# prob.net
KiCad netlist of a schematic drawn in EasyEDA
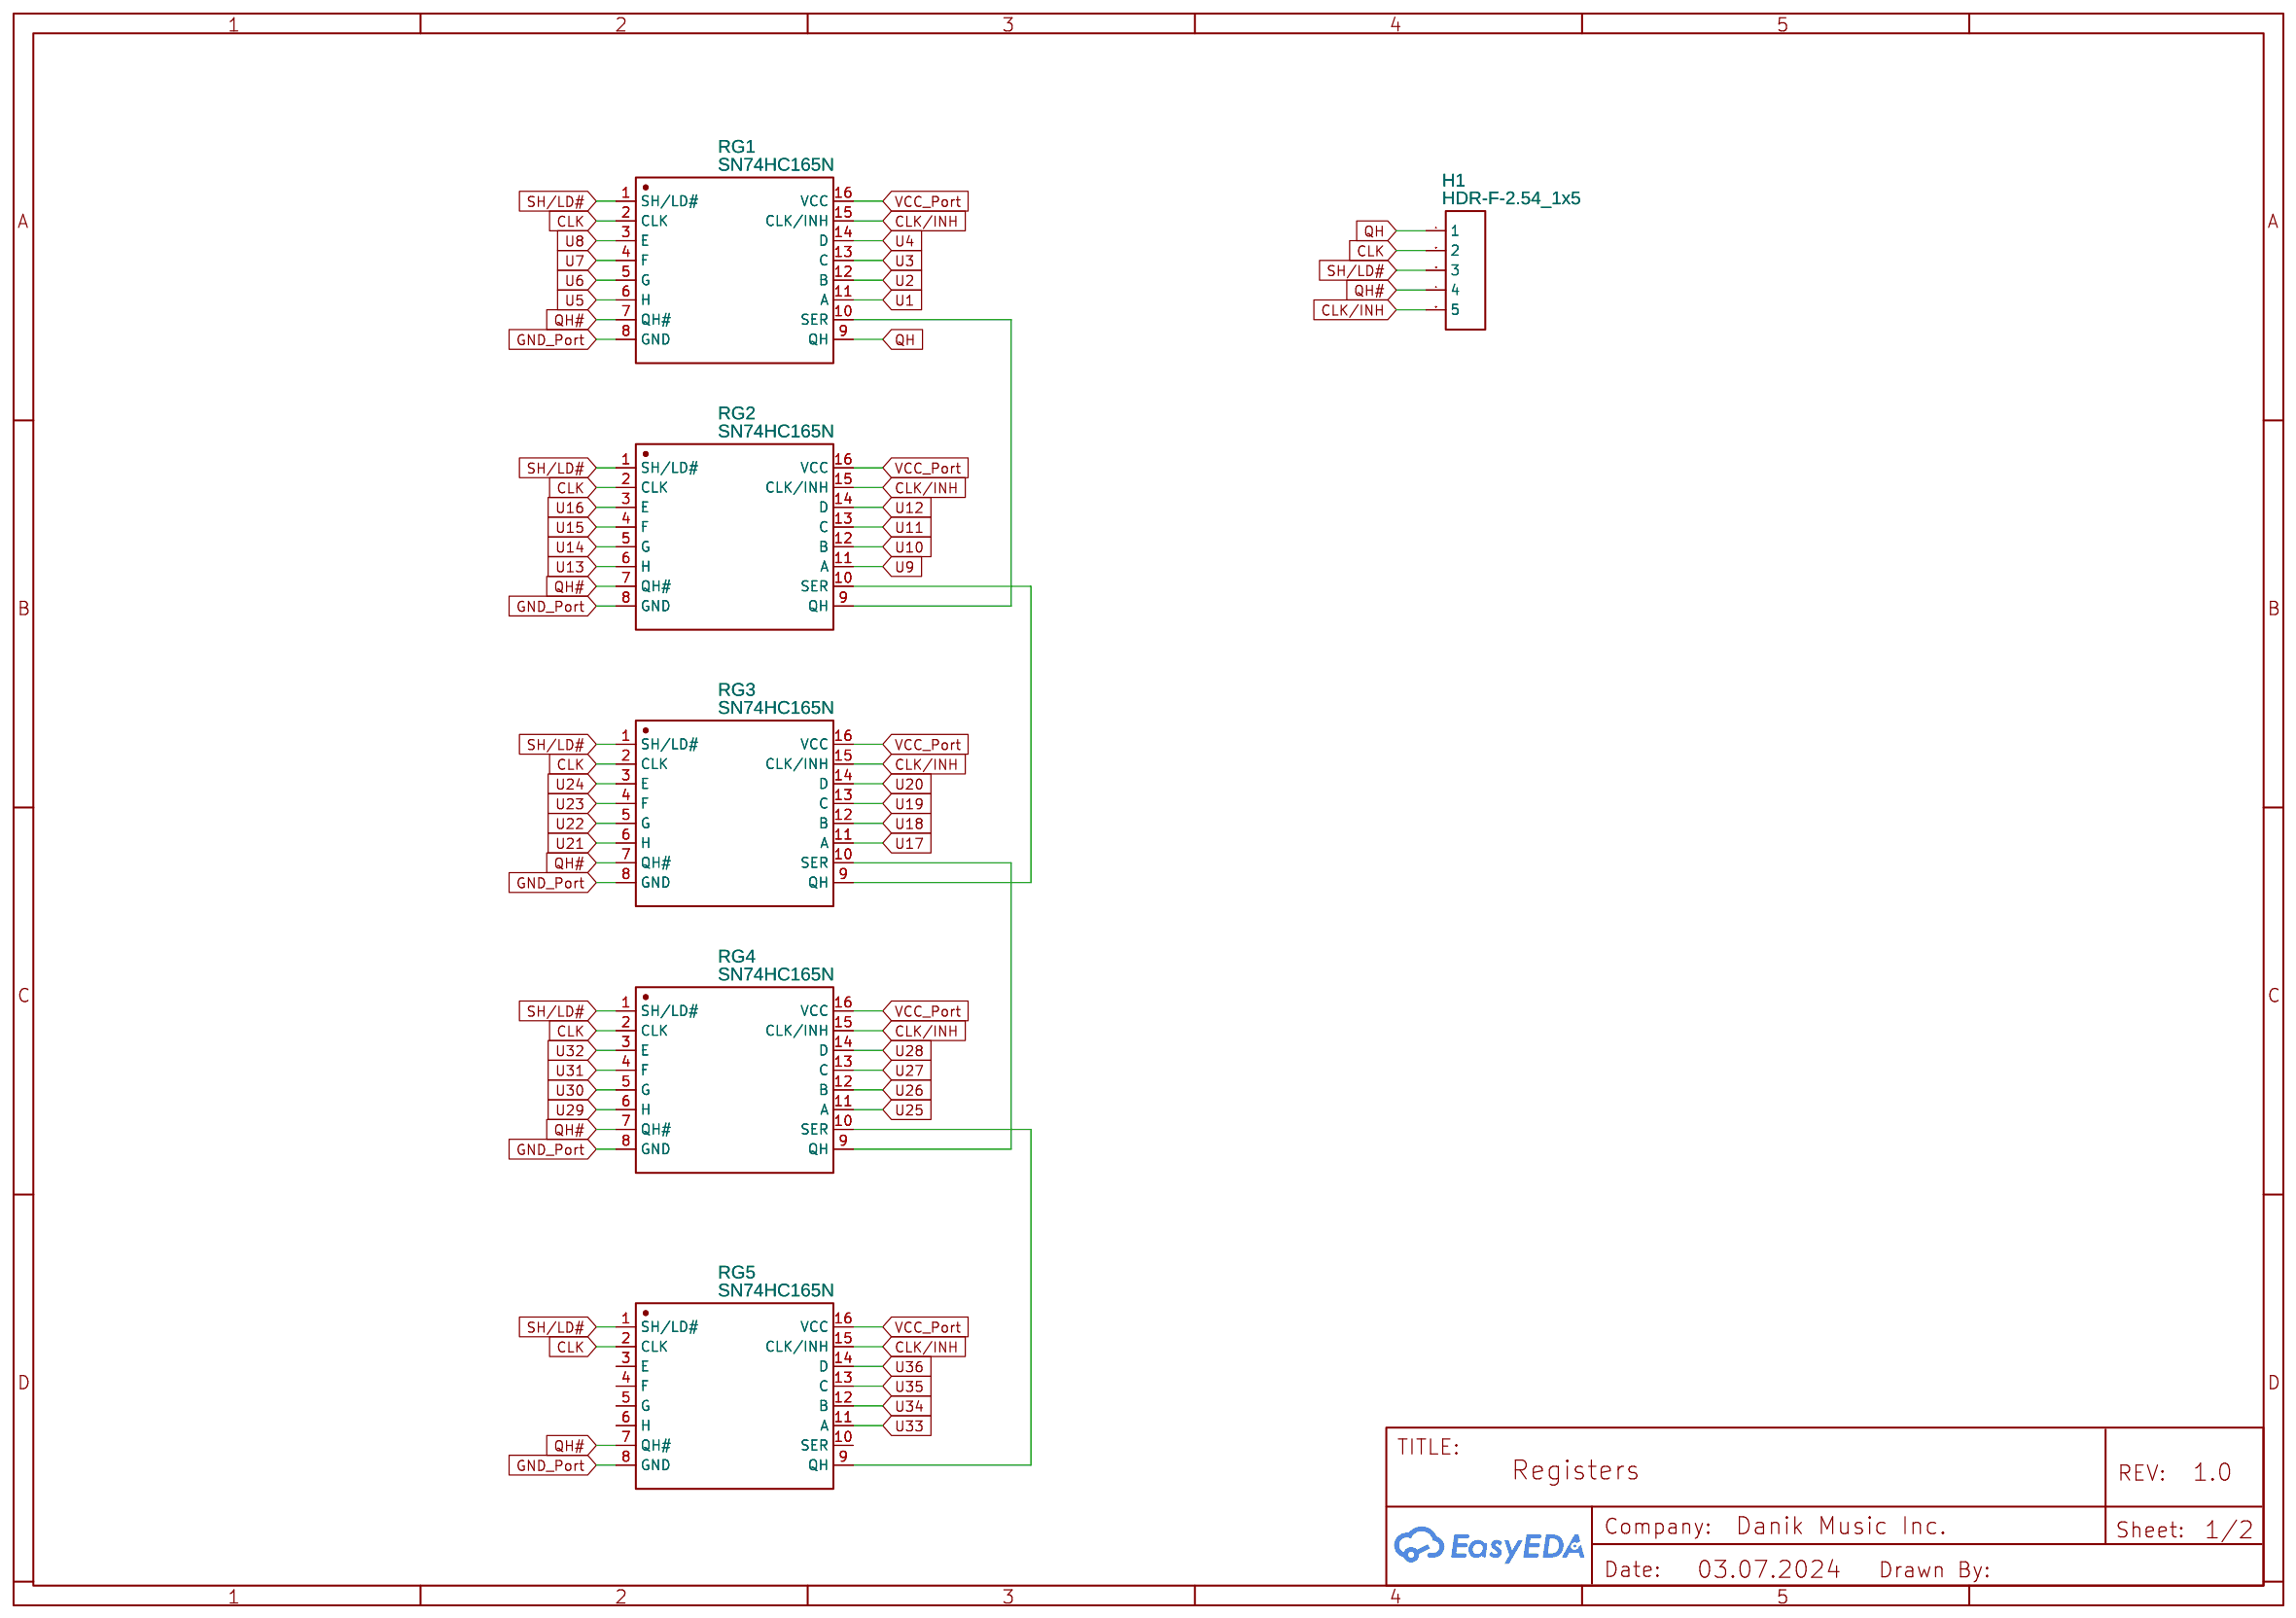
[diagram p0: Регистры]
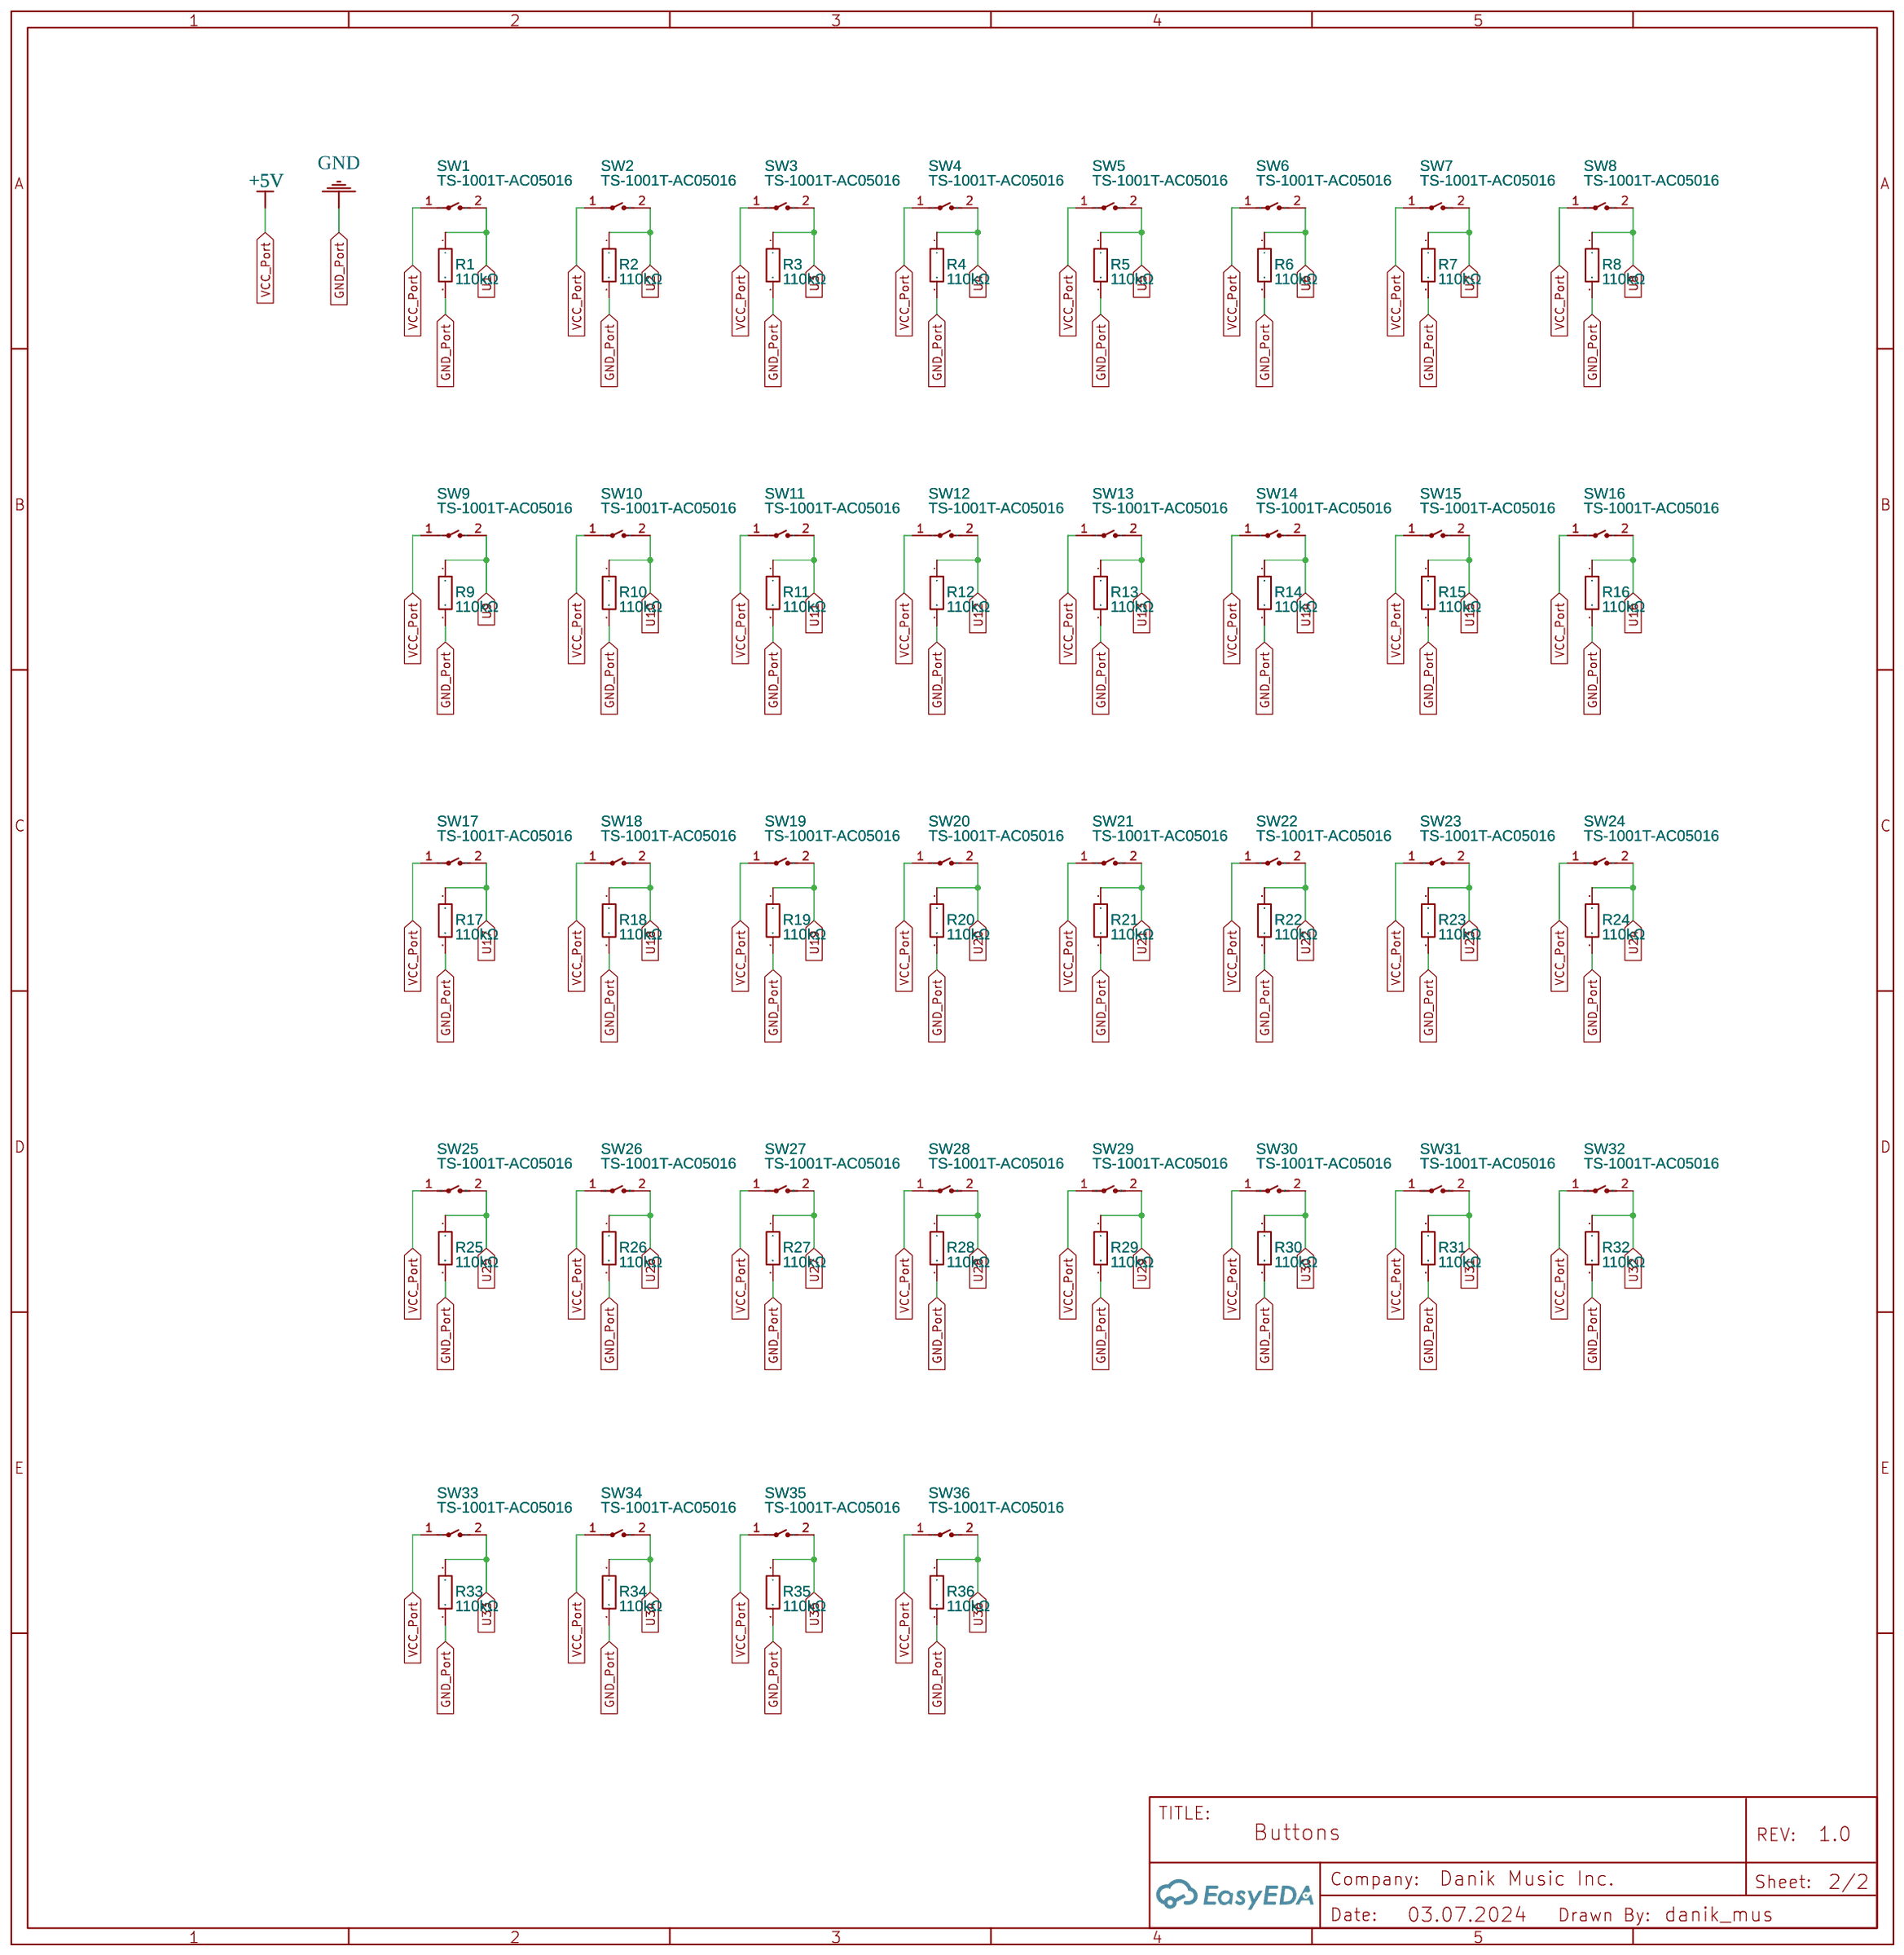
[diagram p1: Кнопки]

(export (version "E")
  (design (tool "Eeschema 10.0.6"))
  (components
    (comp (ref "H1") (value "HDR-F-2.54_1x5") (libsource (lib "") (part "HDR-F-2.54_1x5")))
    (comp (ref "RG1")
      (value "SN74HC165N")
      (fields (field (name "Manufacturer") "TI(德州仪器)"))
      (libsource (lib "") (part "SN74HC165N"))
    )
    (comp (ref "RG2")
      (value "SN74HC165N")
      (fields (field (name "Manufacturer") "TI(德州仪器)"))
      (libsource (lib "") (part "SN74HC165N"))
    )
    (comp (ref "RG3")
      (value "SN74HC165N")
      (fields (field (name "Manufacturer") "TI(德州仪器)"))
      (libsource (lib "") (part "SN74HC165N"))
    )
    (comp (ref "RG4")
      (value "SN74HC165N")
      (fields (field (name "Manufacturer") "TI(德州仪器)"))
      (libsource (lib "") (part "SN74HC165N"))
    )
    (comp (ref "RG5")
      (value "SN74HC165N")
      (fields (field (name "Manufacturer") "TI(德州仪器)"))
      (libsource (lib "") (part "SN74HC165N"))
    )
    (comp (ref "R1")
      (value "110kΩ")
      (fields
        (field (name "Manufacturer Part") "CF1/4W-110KΩ±5% T52")
        (field (name "Manufacturer") "CCO(千志电子)")
      )
      (libsource (lib "") (part "CF1/4W-110KΩ±5% T52"))
    )
    (comp (ref "R2")
      (value "110kΩ")
      (fields
        (field (name "Manufacturer Part") "CF1/4W-110KΩ±5% T52")
        (field (name "Manufacturer") "CCO(千志电子)")
      )
      (libsource (lib "") (part "CF1/4W-110KΩ±5% T52"))
    )
    (comp (ref "R3")
      (value "110kΩ")
      (fields
        (field (name "Manufacturer Part") "CF1/4W-110KΩ±5% T52")
        (field (name "Manufacturer") "CCO(千志电子)")
      )
      (libsource (lib "") (part "CF1/4W-110KΩ±5% T52"))
    )
    (comp (ref "R4")
      (value "110kΩ")
      (fields
        (field (name "Manufacturer Part") "CF1/4W-110KΩ±5% T52")
        (field (name "Manufacturer") "CCO(千志电子)")
      )
      (libsource (lib "") (part "CF1/4W-110KΩ±5% T52"))
    )
    (comp (ref "R5")
      (value "110kΩ")
      (fields
        (field (name "Manufacturer Part") "CF1/4W-110KΩ±5% T52")
        (field (name "Manufacturer") "CCO(千志电子)")
      )
      (libsource (lib "") (part "CF1/4W-110KΩ±5% T52"))
    )
    (comp (ref "R6")
      (value "110kΩ")
      (fields
        (field (name "Manufacturer Part") "CF1/4W-110KΩ±5% T52")
        (field (name "Manufacturer") "CCO(千志电子)")
      )
      (libsource (lib "") (part "CF1/4W-110KΩ±5% T52"))
    )
    (comp (ref "R7")
      (value "110kΩ")
      (fields
        (field (name "Manufacturer Part") "CF1/4W-110KΩ±5% T52")
        (field (name "Manufacturer") "CCO(千志电子)")
      )
      (libsource (lib "") (part "CF1/4W-110KΩ±5% T52"))
    )
    (comp (ref "R8")
      (value "110kΩ")
      (fields
        (field (name "Manufacturer Part") "CF1/4W-110KΩ±5% T52")
        (field (name "Manufacturer") "CCO(千志电子)")
      )
      (libsource (lib "") (part "CF1/4W-110KΩ±5% T52"))
    )
    (comp (ref "R9")
      (value "110kΩ")
      (fields
        (field (name "Manufacturer Part") "CF1/4W-110KΩ±5% T52")
        (field (name "Manufacturer") "CCO(千志电子)")
      )
      (libsource (lib "") (part "CF1/4W-110KΩ±5% T52"))
    )
    (comp (ref "R10")
      (value "110kΩ")
      (fields
        (field (name "Manufacturer Part") "CF1/4W-110KΩ±5% T52")
        (field (name "Manufacturer") "CCO(千志电子)")
      )
      (libsource (lib "") (part "CF1/4W-110KΩ±5% T52"))
    )
    (comp (ref "R11")
      (value "110kΩ")
      (fields
        (field (name "Manufacturer Part") "CF1/4W-110KΩ±5% T52")
        (field (name "Manufacturer") "CCO(千志电子)")
      )
      (libsource (lib "") (part "CF1/4W-110KΩ±5% T52"))
    )
    (comp (ref "R12")
      (value "110kΩ")
      (fields
        (field (name "Manufacturer Part") "CF1/4W-110KΩ±5% T52")
        (field (name "Manufacturer") "CCO(千志电子)")
      )
      (libsource (lib "") (part "CF1/4W-110KΩ±5% T52"))
    )
    (comp (ref "R13")
      (value "110kΩ")
      (fields
        (field (name "Manufacturer Part") "CF1/4W-110KΩ±5% T52")
        (field (name "Manufacturer") "CCO(千志电子)")
      )
      (libsource (lib "") (part "CF1/4W-110KΩ±5% T52"))
    )
    (comp (ref "R14")
      (value "110kΩ")
      (fields
        (field (name "Manufacturer Part") "CF1/4W-110KΩ±5% T52")
        (field (name "Manufacturer") "CCO(千志电子)")
      )
      (libsource (lib "") (part "CF1/4W-110KΩ±5% T52"))
    )
    (comp (ref "R15")
      (value "110kΩ")
      (fields
        (field (name "Manufacturer Part") "CF1/4W-110KΩ±5% T52")
        (field (name "Manufacturer") "CCO(千志电子)")
      )
      (libsource (lib "") (part "CF1/4W-110KΩ±5% T52"))
    )
    (comp (ref "R16")
      (value "110kΩ")
      (fields
        (field (name "Manufacturer Part") "CF1/4W-110KΩ±5% T52")
        (field (name "Manufacturer") "CCO(千志电子)")
      )
      (libsource (lib "") (part "CF1/4W-110KΩ±5% T52"))
    )
    (comp (ref "R17")
      (value "110kΩ")
      (fields
        (field (name "Manufacturer Part") "CF1/4W-110KΩ±5% T52")
        (field (name "Manufacturer") "CCO(千志电子)")
      )
      (libsource (lib "") (part "CF1/4W-110KΩ±5% T52"))
    )
    (comp (ref "R18")
      (value "110kΩ")
      (fields
        (field (name "Manufacturer Part") "CF1/4W-110KΩ±5% T52")
        (field (name "Manufacturer") "CCO(千志电子)")
      )
      (libsource (lib "") (part "CF1/4W-110KΩ±5% T52"))
    )
    (comp (ref "R19")
      (value "110kΩ")
      (fields
        (field (name "Manufacturer Part") "CF1/4W-110KΩ±5% T52")
        (field (name "Manufacturer") "CCO(千志电子)")
      )
      (libsource (lib "") (part "CF1/4W-110KΩ±5% T52"))
    )
    (comp (ref "R20")
      (value "110kΩ")
      (fields
        (field (name "Manufacturer Part") "CF1/4W-110KΩ±5% T52")
        (field (name "Manufacturer") "CCO(千志电子)")
      )
      (libsource (lib "") (part "CF1/4W-110KΩ±5% T52"))
    )
    (comp (ref "R21")
      (value "110kΩ")
      (fields
        (field (name "Manufacturer Part") "CF1/4W-110KΩ±5% T52")
        (field (name "Manufacturer") "CCO(千志电子)")
      )
      (libsource (lib "") (part "CF1/4W-110KΩ±5% T52"))
    )
    (comp (ref "R22")
      (value "110kΩ")
      (fields
        (field (name "Manufacturer Part") "CF1/4W-110KΩ±5% T52")
        (field (name "Manufacturer") "CCO(千志电子)")
      )
      (libsource (lib "") (part "CF1/4W-110KΩ±5% T52"))
    )
    (comp (ref "R23")
      (value "110kΩ")
      (fields
        (field (name "Manufacturer Part") "CF1/4W-110KΩ±5% T52")
        (field (name "Manufacturer") "CCO(千志电子)")
      )
      (libsource (lib "") (part "CF1/4W-110KΩ±5% T52"))
    )
    (comp (ref "R24")
      (value "110kΩ")
      (fields
        (field (name "Manufacturer Part") "CF1/4W-110KΩ±5% T52")
        (field (name "Manufacturer") "CCO(千志电子)")
      )
      (libsource (lib "") (part "CF1/4W-110KΩ±5% T52"))
    )
    (comp (ref "R25")
      (value "110kΩ")
      (fields
        (field (name "Manufacturer Part") "CF1/4W-110KΩ±5% T52")
        (field (name "Manufacturer") "CCO(千志电子)")
      )
      (libsource (lib "") (part "CF1/4W-110KΩ±5% T52"))
    )
    (comp (ref "R26")
      (value "110kΩ")
      (fields
        (field (name "Manufacturer Part") "CF1/4W-110KΩ±5% T52")
        (field (name "Manufacturer") "CCO(千志电子)")
      )
      (libsource (lib "") (part "CF1/4W-110KΩ±5% T52"))
    )
    (comp (ref "R27")
      (value "110kΩ")
      (fields
        (field (name "Manufacturer Part") "CF1/4W-110KΩ±5% T52")
        (field (name "Manufacturer") "CCO(千志电子)")
      )
      (libsource (lib "") (part "CF1/4W-110KΩ±5% T52"))
    )
    (comp (ref "R28")
      (value "110kΩ")
      (fields
        (field (name "Manufacturer Part") "CF1/4W-110KΩ±5% T52")
        (field (name "Manufacturer") "CCO(千志电子)")
      )
      (libsource (lib "") (part "CF1/4W-110KΩ±5% T52"))
    )
    (comp (ref "R29")
      (value "110kΩ")
      (fields
        (field (name "Manufacturer Part") "CF1/4W-110KΩ±5% T52")
        (field (name "Manufacturer") "CCO(千志电子)")
      )
      (libsource (lib "") (part "CF1/4W-110KΩ±5% T52"))
    )
    (comp (ref "R30")
      (value "110kΩ")
      (fields
        (field (name "Manufacturer Part") "CF1/4W-110KΩ±5% T52")
        (field (name "Manufacturer") "CCO(千志电子)")
      )
      (libsource (lib "") (part "CF1/4W-110KΩ±5% T52"))
    )
    (comp (ref "R31")
      (value "110kΩ")
      (fields
        (field (name "Manufacturer Part") "CF1/4W-110KΩ±5% T52")
        (field (name "Manufacturer") "CCO(千志电子)")
      )
      (libsource (lib "") (part "CF1/4W-110KΩ±5% T52"))
    )
    (comp (ref "R32")
      (value "110kΩ")
      (fields
        (field (name "Manufacturer Part") "CF1/4W-110KΩ±5% T52")
        (field (name "Manufacturer") "CCO(千志电子)")
      )
      (libsource (lib "") (part "CF1/4W-110KΩ±5% T52"))
    )
    (comp (ref "R33")
      (value "110kΩ")
      (fields
        (field (name "Manufacturer Part") "CF1/4W-110KΩ±5% T52")
        (field (name "Manufacturer") "CCO(千志电子)")
      )
      (libsource (lib "") (part "CF1/4W-110KΩ±5% T52"))
    )
    (comp (ref "R34")
      (value "110kΩ")
      (fields
        (field (name "Manufacturer Part") "CF1/4W-110KΩ±5% T52")
        (field (name "Manufacturer") "CCO(千志电子)")
      )
      (libsource (lib "") (part "CF1/4W-110KΩ±5% T52"))
    )
    (comp (ref "R35")
      (value "110kΩ")
      (fields
        (field (name "Manufacturer Part") "CF1/4W-110KΩ±5% T52")
        (field (name "Manufacturer") "CCO(千志电子)")
      )
      (libsource (lib "") (part "CF1/4W-110KΩ±5% T52"))
    )
    (comp (ref "R36")
      (value "110kΩ")
      (fields
        (field (name "Manufacturer Part") "CF1/4W-110KΩ±5% T52")
        (field (name "Manufacturer") "CCO(千志电子)")
      )
      (libsource (lib "") (part "CF1/4W-110KΩ±5% T52"))
    )
    (comp (ref "SW1")
      (value "TS-1001T-AC05016")
      (fields (field (name "Manufacturer") "XUNPU(讯普)"))
      (libsource (lib "") (part "TS-1001T-AC05016"))
    )
    (comp (ref "SW2")
      (value "TS-1001T-AC05016")
      (fields (field (name "Manufacturer") "XUNPU(讯普)"))
      (libsource (lib "") (part "TS-1001T-AC05016"))
    )
    (comp (ref "SW3")
      (value "TS-1001T-AC05016")
      (fields (field (name "Manufacturer") "XUNPU(讯普)"))
      (libsource (lib "") (part "TS-1001T-AC05016"))
    )
    (comp (ref "SW4")
      (value "TS-1001T-AC05016")
      (fields (field (name "Manufacturer") "XUNPU(讯普)"))
      (libsource (lib "") (part "TS-1001T-AC05016"))
    )
    (comp (ref "SW5")
      (value "TS-1001T-AC05016")
      (fields (field (name "Manufacturer") "XUNPU(讯普)"))
      (libsource (lib "") (part "TS-1001T-AC05016"))
    )
    (comp (ref "SW6")
      (value "TS-1001T-AC05016")
      (fields (field (name "Manufacturer") "XUNPU(讯普)"))
      (libsource (lib "") (part "TS-1001T-AC05016"))
    )
    (comp (ref "SW7")
      (value "TS-1001T-AC05016")
      (fields (field (name "Manufacturer") "XUNPU(讯普)"))
      (libsource (lib "") (part "TS-1001T-AC05016"))
    )
    (comp (ref "SW8")
      (value "TS-1001T-AC05016")
      (fields (field (name "Manufacturer") "XUNPU(讯普)"))
      (libsource (lib "") (part "TS-1001T-AC05016"))
    )
    (comp (ref "SW9")
      (value "TS-1001T-AC05016")
      (fields (field (name "Manufacturer") "XUNPU(讯普)"))
      (libsource (lib "") (part "TS-1001T-AC05016"))
    )
    (comp (ref "SW10")
      (value "TS-1001T-AC05016")
      (fields (field (name "Manufacturer") "XUNPU(讯普)"))
      (libsource (lib "") (part "TS-1001T-AC05016"))
    )
    (comp (ref "SW11")
      (value "TS-1001T-AC05016")
      (fields (field (name "Manufacturer") "XUNPU(讯普)"))
      (libsource (lib "") (part "TS-1001T-AC05016"))
    )
    (comp (ref "SW12")
      (value "TS-1001T-AC05016")
      (fields (field (name "Manufacturer") "XUNPU(讯普)"))
      (libsource (lib "") (part "TS-1001T-AC05016"))
    )
    (comp (ref "SW13")
      (value "TS-1001T-AC05016")
      (fields (field (name "Manufacturer") "XUNPU(讯普)"))
      (libsource (lib "") (part "TS-1001T-AC05016"))
    )
    (comp (ref "SW14")
      (value "TS-1001T-AC05016")
      (fields (field (name "Manufacturer") "XUNPU(讯普)"))
      (libsource (lib "") (part "TS-1001T-AC05016"))
    )
    (comp (ref "SW15")
      (value "TS-1001T-AC05016")
      (fields (field (name "Manufacturer") "XUNPU(讯普)"))
      (libsource (lib "") (part "TS-1001T-AC05016"))
    )
    (comp (ref "SW16")
      (value "TS-1001T-AC05016")
      (fields (field (name "Manufacturer") "XUNPU(讯普)"))
      (libsource (lib "") (part "TS-1001T-AC05016"))
    )
    (comp (ref "SW17")
      (value "TS-1001T-AC05016")
      (fields (field (name "Manufacturer") "XUNPU(讯普)"))
      (libsource (lib "") (part "TS-1001T-AC05016"))
    )
    (comp (ref "SW18")
      (value "TS-1001T-AC05016")
      (fields (field (name "Manufacturer") "XUNPU(讯普)"))
      (libsource (lib "") (part "TS-1001T-AC05016"))
    )
    (comp (ref "SW19")
      (value "TS-1001T-AC05016")
      (fields (field (name "Manufacturer") "XUNPU(讯普)"))
      (libsource (lib "") (part "TS-1001T-AC05016"))
    )
    (comp (ref "SW20")
      (value "TS-1001T-AC05016")
      (fields (field (name "Manufacturer") "XUNPU(讯普)"))
      (libsource (lib "") (part "TS-1001T-AC05016"))
    )
    (comp (ref "SW21")
      (value "TS-1001T-AC05016")
      (fields (field (name "Manufacturer") "XUNPU(讯普)"))
      (libsource (lib "") (part "TS-1001T-AC05016"))
    )
    (comp (ref "SW22")
      (value "TS-1001T-AC05016")
      (fields (field (name "Manufacturer") "XUNPU(讯普)"))
      (libsource (lib "") (part "TS-1001T-AC05016"))
    )
    (comp (ref "SW23")
      (value "TS-1001T-AC05016")
      (fields (field (name "Manufacturer") "XUNPU(讯普)"))
      (libsource (lib "") (part "TS-1001T-AC05016"))
    )
    (comp (ref "SW24")
      (value "TS-1001T-AC05016")
      (fields (field (name "Manufacturer") "XUNPU(讯普)"))
      (libsource (lib "") (part "TS-1001T-AC05016"))
    )
    (comp (ref "SW25")
      (value "TS-1001T-AC05016")
      (fields (field (name "Manufacturer") "XUNPU(讯普)"))
      (libsource (lib "") (part "TS-1001T-AC05016"))
    )
    (comp (ref "SW26")
      (value "TS-1001T-AC05016")
      (fields (field (name "Manufacturer") "XUNPU(讯普)"))
      (libsource (lib "") (part "TS-1001T-AC05016"))
    )
    (comp (ref "SW27")
      (value "TS-1001T-AC05016")
      (fields (field (name "Manufacturer") "XUNPU(讯普)"))
      (libsource (lib "") (part "TS-1001T-AC05016"))
    )
    (comp (ref "SW28")
      (value "TS-1001T-AC05016")
      (fields (field (name "Manufacturer") "XUNPU(讯普)"))
      (libsource (lib "") (part "TS-1001T-AC05016"))
    )
    (comp (ref "SW29")
      (value "TS-1001T-AC05016")
      (fields (field (name "Manufacturer") "XUNPU(讯普)"))
      (libsource (lib "") (part "TS-1001T-AC05016"))
    )
    (comp (ref "SW30")
      (value "TS-1001T-AC05016")
      (fields (field (name "Manufacturer") "XUNPU(讯普)"))
      (libsource (lib "") (part "TS-1001T-AC05016"))
    )
    (comp (ref "SW31")
      (value "TS-1001T-AC05016")
      (fields (field (name "Manufacturer") "XUNPU(讯普)"))
      (libsource (lib "") (part "TS-1001T-AC05016"))
    )
    (comp (ref "SW32")
      (value "TS-1001T-AC05016")
      (fields (field (name "Manufacturer") "XUNPU(讯普)"))
      (libsource (lib "") (part "TS-1001T-AC05016"))
    )
    (comp (ref "SW33")
      (value "TS-1001T-AC05016")
      (fields (field (name "Manufacturer") "XUNPU(讯普)"))
      (libsource (lib "") (part "TS-1001T-AC05016"))
    )
    (comp (ref "SW34")
      (value "TS-1001T-AC05016")
      (fields (field (name "Manufacturer") "XUNPU(讯普)"))
      (libsource (lib "") (part "TS-1001T-AC05016"))
    )
    (comp (ref "SW35")
      (value "TS-1001T-AC05016")
      (fields (field (name "Manufacturer") "XUNPU(讯普)"))
      (libsource (lib "") (part "TS-1001T-AC05016"))
    )
    (comp (ref "SW36")
      (value "TS-1001T-AC05016")
      (fields (field (name "Manufacturer") "XUNPU(讯普)"))
      (libsource (lib "") (part "TS-1001T-AC05016"))
    )
  )
  (nets
    (net (code "1") (name "CLK") (class "Default")
      (node (ref "H1") (pin "2") (pinfunction "2_2") (pintype "unspecified"))
      (node (ref "RG1") (pin "2") (pinfunction "CLK_2") (pintype "unspecified"))
      (node (ref "RG2") (pin "2") (pinfunction "CLK_2") (pintype "unspecified"))
      (node (ref "RG3") (pin "2") (pinfunction "CLK_2") (pintype "unspecified"))
      (node (ref "RG4") (pin "2") (pinfunction "CLK_2") (pintype "unspecified"))
      (node (ref "RG5") (pin "2") (pinfunction "CLK_2") (pintype "unspecified"))
    )
    (net (code "2") (name "CLK{slash}INH") (class "Default")
      (node (ref "H1") (pin "5") (pinfunction "5_5") (pintype "unspecified"))
      (node (ref "RG1") (pin "15") (pinfunction "CLK/INH_15") (pintype "unspecified"))
      (node (ref "RG2") (pin "15") (pinfunction "CLK/INH_15") (pintype "unspecified"))
      (node (ref "RG3") (pin "15") (pinfunction "CLK/INH_15") (pintype "unspecified"))
      (node (ref "RG4") (pin "15") (pinfunction "CLK/INH_15") (pintype "unspecified"))
      (node (ref "RG5") (pin "15") (pinfunction "CLK/INH_15") (pintype "unspecified"))
    )
    (net (code "3") (name "GND_Port") (class "Default")
      (node (ref "R1") (pin "2") (pinfunction "2_2") (pintype "unspecified"))
      (node (ref "R10") (pin "2") (pinfunction "2_2") (pintype "unspecified"))
      (node (ref "R11") (pin "2") (pinfunction "2_2") (pintype "unspecified"))
      (node (ref "R12") (pin "2") (pinfunction "2_2") (pintype "unspecified"))
      (node (ref "R13") (pin "2") (pinfunction "2_2") (pintype "unspecified"))
      (node (ref "R14") (pin "2") (pinfunction "2_2") (pintype "unspecified"))
      (node (ref "R15") (pin "2") (pinfunction "2_2") (pintype "unspecified"))
      (node (ref "R16") (pin "2") (pinfunction "2_2") (pintype "unspecified"))
      (node (ref "R17") (pin "2") (pinfunction "2_2") (pintype "unspecified"))
      (node (ref "R18") (pin "2") (pinfunction "2_2") (pintype "unspecified"))
      (node (ref "R19") (pin "2") (pinfunction "2_2") (pintype "unspecified"))
      (node (ref "R2") (pin "2") (pinfunction "2_2") (pintype "unspecified"))
      (node (ref "R20") (pin "2") (pinfunction "2_2") (pintype "unspecified"))
      (node (ref "R21") (pin "2") (pinfunction "2_2") (pintype "unspecified"))
      (node (ref "R22") (pin "2") (pinfunction "2_2") (pintype "unspecified"))
      (node (ref "R23") (pin "2") (pinfunction "2_2") (pintype "unspecified"))
      (node (ref "R24") (pin "2") (pinfunction "2_2") (pintype "unspecified"))
      (node (ref "R25") (pin "2") (pinfunction "2_2") (pintype "unspecified"))
      (node (ref "R26") (pin "2") (pinfunction "2_2") (pintype "unspecified"))
      (node (ref "R27") (pin "2") (pinfunction "2_2") (pintype "unspecified"))
      (node (ref "R28") (pin "2") (pinfunction "2_2") (pintype "unspecified"))
      (node (ref "R29") (pin "2") (pinfunction "2_2") (pintype "unspecified"))
      (node (ref "R3") (pin "2") (pinfunction "2_2") (pintype "unspecified"))
      (node (ref "R30") (pin "2") (pinfunction "2_2") (pintype "unspecified"))
      (node (ref "R31") (pin "2") (pinfunction "2_2") (pintype "unspecified"))
      (node (ref "R32") (pin "2") (pinfunction "2_2") (pintype "unspecified"))
      (node (ref "R33") (pin "2") (pinfunction "2_2") (pintype "unspecified"))
      (node (ref "R34") (pin "2") (pinfunction "2_2") (pintype "unspecified"))
      (node (ref "R35") (pin "2") (pinfunction "2_2") (pintype "unspecified"))
      (node (ref "R36") (pin "2") (pinfunction "2_2") (pintype "unspecified"))
      (node (ref "R4") (pin "2") (pinfunction "2_2") (pintype "unspecified"))
      (node (ref "R5") (pin "2") (pinfunction "2_2") (pintype "unspecified"))
      (node (ref "R6") (pin "2") (pinfunction "2_2") (pintype "unspecified"))
      (node (ref "R7") (pin "2") (pinfunction "2_2") (pintype "unspecified"))
      (node (ref "R8") (pin "2") (pinfunction "2_2") (pintype "unspecified"))
      (node (ref "R9") (pin "2") (pinfunction "2_2") (pintype "unspecified"))
      (node (ref "RG1") (pin "8") (pinfunction "GND_8") (pintype "unspecified"))
      (node (ref "RG2") (pin "8") (pinfunction "GND_8") (pintype "unspecified"))
      (node (ref "RG3") (pin "8") (pinfunction "GND_8") (pintype "unspecified"))
      (node (ref "RG4") (pin "8") (pinfunction "GND_8") (pintype "unspecified"))
      (node (ref "RG5") (pin "8") (pinfunction "GND_8") (pintype "unspecified"))
    )
    (net (code "4") (name "Net-(RG1-SER)") (class "Default")
      (node (ref "RG1") (pin "10") (pinfunction "SER_10") (pintype "unspecified"))
      (node (ref "RG2") (pin "9") (pinfunction "QH_9") (pintype "unspecified"))
    )
    (net (code "5") (name "Net-(RG2-SER)") (class "Default")
      (node (ref "RG2") (pin "10") (pinfunction "SER_10") (pintype "unspecified"))
      (node (ref "RG3") (pin "9") (pinfunction "QH_9") (pintype "unspecified"))
    )
    (net (code "6") (name "Net-(RG3-SER)") (class "Default")
      (node (ref "RG3") (pin "10") (pinfunction "SER_10") (pintype "unspecified"))
      (node (ref "RG4") (pin "9") (pinfunction "QH_9") (pintype "unspecified"))
    )
    (net (code "7") (name "Net-(RG4-SER)") (class "Default")
      (node (ref "RG4") (pin "10") (pinfunction "SER_10") (pintype "unspecified"))
      (node (ref "RG5") (pin "9") (pinfunction "QH_9") (pintype "unspecified"))
    )
    (net (code "8") (name "QH") (class "Default")
      (node (ref "H1") (pin "1") (pinfunction "1_1") (pintype "unspecified"))
      (node (ref "RG1") (pin "9") (pinfunction "QH_9") (pintype "unspecified"))
    )
    (net (code "9") (name "QH#") (class "Default")
      (node (ref "H1") (pin "4") (pinfunction "4_4") (pintype "unspecified"))
      (node (ref "RG1") (pin "7") (pinfunction "QH#_7") (pintype "unspecified"))
      (node (ref "RG2") (pin "7") (pinfunction "QH#_7") (pintype "unspecified"))
      (node (ref "RG3") (pin "7") (pinfunction "QH#_7") (pintype "unspecified"))
      (node (ref "RG4") (pin "7") (pinfunction "QH#_7") (pintype "unspecified"))
      (node (ref "RG5") (pin "7") (pinfunction "QH#_7") (pintype "unspecified"))
    )
    (net (code "10") (name "SH{slash}LD#") (class "Default")
      (node (ref "H1") (pin "3") (pinfunction "3_3") (pintype "unspecified"))
      (node (ref "RG1") (pin "1") (pinfunction "SH/LD#_1") (pintype "unspecified"))
      (node (ref "RG2") (pin "1") (pinfunction "SH/LD#_1") (pintype "unspecified"))
      (node (ref "RG3") (pin "1") (pinfunction "SH/LD#_1") (pintype "unspecified"))
      (node (ref "RG4") (pin "1") (pinfunction "SH/LD#_1") (pintype "unspecified"))
      (node (ref "RG5") (pin "1") (pinfunction "SH/LD#_1") (pintype "unspecified"))
    )
    (net (code "11") (name "U1") (class "Default")
      (node (ref "R1") (pin "1") (pinfunction "1_1") (pintype "unspecified"))
      (node (ref "RG1") (pin "11") (pinfunction "A_11") (pintype "unspecified"))
      (node (ref "SW1") (pin "2") (pinfunction "2_2") (pintype "unspecified"))
    )
    (net (code "12") (name "U2") (class "Default")
      (node (ref "R2") (pin "1") (pinfunction "1_1") (pintype "unspecified"))
      (node (ref "RG1") (pin "12") (pinfunction "B_12") (pintype "unspecified"))
      (node (ref "SW2") (pin "2") (pinfunction "2_2") (pintype "unspecified"))
    )
    (net (code "13") (name "U3") (class "Default")
      (node (ref "R3") (pin "1") (pinfunction "1_1") (pintype "unspecified"))
      (node (ref "RG1") (pin "13") (pinfunction "C_13") (pintype "unspecified"))
      (node (ref "SW3") (pin "2") (pinfunction "2_2") (pintype "unspecified"))
    )
    (net (code "14") (name "U4") (class "Default")
      (node (ref "R4") (pin "1") (pinfunction "1_1") (pintype "unspecified"))
      (node (ref "RG1") (pin "14") (pinfunction "D_14") (pintype "unspecified"))
      (node (ref "SW4") (pin "2") (pinfunction "2_2") (pintype "unspecified"))
    )
    (net (code "15") (name "U5") (class "Default")
      (node (ref "R5") (pin "1") (pinfunction "1_1") (pintype "unspecified"))
      (node (ref "RG1") (pin "6") (pinfunction "H_6") (pintype "unspecified"))
      (node (ref "SW5") (pin "2") (pinfunction "2_2") (pintype "unspecified"))
    )
    (net (code "16") (name "U6") (class "Default")
      (node (ref "R6") (pin "1") (pinfunction "1_1") (pintype "unspecified"))
      (node (ref "RG1") (pin "5") (pinfunction "G_5") (pintype "unspecified"))
      (node (ref "SW6") (pin "2") (pinfunction "2_2") (pintype "unspecified"))
    )
    (net (code "17") (name "U7") (class "Default")
      (node (ref "R7") (pin "1") (pinfunction "1_1") (pintype "unspecified"))
      (node (ref "RG1") (pin "4") (pinfunction "F_4") (pintype "unspecified"))
      (node (ref "SW7") (pin "2") (pinfunction "2_2") (pintype "unspecified"))
    )
    (net (code "18") (name "U8") (class "Default")
      (node (ref "R8") (pin "1") (pinfunction "1_1") (pintype "unspecified"))
      (node (ref "RG1") (pin "3") (pinfunction "E_3") (pintype "unspecified"))
      (node (ref "SW8") (pin "2") (pinfunction "2_2") (pintype "unspecified"))
    )
    (net (code "19") (name "U9") (class "Default")
      (node (ref "R9") (pin "1") (pinfunction "1_1") (pintype "unspecified"))
      (node (ref "RG2") (pin "11") (pinfunction "A_11") (pintype "unspecified"))
      (node (ref "SW9") (pin "2") (pinfunction "2_2") (pintype "unspecified"))
    )
    (net (code "20") (name "U10") (class "Default")
      (node (ref "R10") (pin "1") (pinfunction "1_1") (pintype "unspecified"))
      (node (ref "RG2") (pin "12") (pinfunction "B_12") (pintype "unspecified"))
      (node (ref "SW10") (pin "2") (pinfunction "2_2") (pintype "unspecified"))
    )
    (net (code "21") (name "U11") (class "Default")
      (node (ref "R11") (pin "1") (pinfunction "1_1") (pintype "unspecified"))
      (node (ref "RG2") (pin "13") (pinfunction "C_13") (pintype "unspecified"))
      (node (ref "SW11") (pin "2") (pinfunction "2_2") (pintype "unspecified"))
    )
    (net (code "22") (name "U12") (class "Default")
      (node (ref "R12") (pin "1") (pinfunction "1_1") (pintype "unspecified"))
      (node (ref "RG2") (pin "14") (pinfunction "D_14") (pintype "unspecified"))
      (node (ref "SW12") (pin "2") (pinfunction "2_2") (pintype "unspecified"))
    )
    (net (code "23") (name "U13") (class "Default")
      (node (ref "R13") (pin "1") (pinfunction "1_1") (pintype "unspecified"))
      (node (ref "RG2") (pin "6") (pinfunction "H_6") (pintype "unspecified"))
      (node (ref "SW13") (pin "2") (pinfunction "2_2") (pintype "unspecified"))
    )
    (net (code "24") (name "U14") (class "Default")
      (node (ref "R14") (pin "1") (pinfunction "1_1") (pintype "unspecified"))
      (node (ref "RG2") (pin "5") (pinfunction "G_5") (pintype "unspecified"))
      (node (ref "SW14") (pin "2") (pinfunction "2_2") (pintype "unspecified"))
    )
    (net (code "25") (name "U15") (class "Default")
      (node (ref "R15") (pin "1") (pinfunction "1_1") (pintype "unspecified"))
      (node (ref "RG2") (pin "4") (pinfunction "F_4") (pintype "unspecified"))
      (node (ref "SW15") (pin "2") (pinfunction "2_2") (pintype "unspecified"))
    )
    (net (code "26") (name "U16") (class "Default")
      (node (ref "R16") (pin "1") (pinfunction "1_1") (pintype "unspecified"))
      (node (ref "RG2") (pin "3") (pinfunction "E_3") (pintype "unspecified"))
      (node (ref "SW16") (pin "2") (pinfunction "2_2") (pintype "unspecified"))
    )
    (net (code "27") (name "U17") (class "Default")
      (node (ref "R17") (pin "1") (pinfunction "1_1") (pintype "unspecified"))
      (node (ref "RG3") (pin "11") (pinfunction "A_11") (pintype "unspecified"))
      (node (ref "SW17") (pin "2") (pinfunction "2_2") (pintype "unspecified"))
    )
    (net (code "28") (name "U18") (class "Default")
      (node (ref "R18") (pin "1") (pinfunction "1_1") (pintype "unspecified"))
      (node (ref "RG3") (pin "12") (pinfunction "B_12") (pintype "unspecified"))
      (node (ref "SW18") (pin "2") (pinfunction "2_2") (pintype "unspecified"))
    )
    (net (code "29") (name "U19") (class "Default")
      (node (ref "R19") (pin "1") (pinfunction "1_1") (pintype "unspecified"))
      (node (ref "RG3") (pin "13") (pinfunction "C_13") (pintype "unspecified"))
      (node (ref "SW19") (pin "2") (pinfunction "2_2") (pintype "unspecified"))
    )
    (net (code "30") (name "U20") (class "Default")
      (node (ref "R20") (pin "1") (pinfunction "1_1") (pintype "unspecified"))
      (node (ref "RG3") (pin "14") (pinfunction "D_14") (pintype "unspecified"))
      (node (ref "SW20") (pin "2") (pinfunction "2_2") (pintype "unspecified"))
    )
    (net (code "31") (name "U21") (class "Default")
      (node (ref "R21") (pin "1") (pinfunction "1_1") (pintype "unspecified"))
      (node (ref "RG3") (pin "6") (pinfunction "H_6") (pintype "unspecified"))
      (node (ref "SW21") (pin "2") (pinfunction "2_2") (pintype "unspecified"))
    )
    (net (code "32") (name "U22") (class "Default")
      (node (ref "R22") (pin "1") (pinfunction "1_1") (pintype "unspecified"))
      (node (ref "RG3") (pin "5") (pinfunction "G_5") (pintype "unspecified"))
      (node (ref "SW22") (pin "2") (pinfunction "2_2") (pintype "unspecified"))
    )
    (net (code "33") (name "U23") (class "Default")
      (node (ref "R23") (pin "1") (pinfunction "1_1") (pintype "unspecified"))
      (node (ref "RG3") (pin "4") (pinfunction "F_4") (pintype "unspecified"))
      (node (ref "SW23") (pin "2") (pinfunction "2_2") (pintype "unspecified"))
    )
    (net (code "34") (name "U24") (class "Default")
      (node (ref "R24") (pin "1") (pinfunction "1_1") (pintype "unspecified"))
      (node (ref "RG3") (pin "3") (pinfunction "E_3") (pintype "unspecified"))
      (node (ref "SW24") (pin "2") (pinfunction "2_2") (pintype "unspecified"))
    )
    (net (code "35") (name "U25") (class "Default")
      (node (ref "R25") (pin "1") (pinfunction "1_1") (pintype "unspecified"))
      (node (ref "RG4") (pin "11") (pinfunction "A_11") (pintype "unspecified"))
      (node (ref "SW25") (pin "2") (pinfunction "2_2") (pintype "unspecified"))
    )
    (net (code "36") (name "U26") (class "Default")
      (node (ref "R26") (pin "1") (pinfunction "1_1") (pintype "unspecified"))
      (node (ref "RG4") (pin "12") (pinfunction "B_12") (pintype "unspecified"))
      (node (ref "SW26") (pin "2") (pinfunction "2_2") (pintype "unspecified"))
    )
    (net (code "37") (name "U27") (class "Default")
      (node (ref "R27") (pin "1") (pinfunction "1_1") (pintype "unspecified"))
      (node (ref "RG4") (pin "13") (pinfunction "C_13") (pintype "unspecified"))
      (node (ref "SW27") (pin "2") (pinfunction "2_2") (pintype "unspecified"))
    )
    (net (code "38") (name "U28") (class "Default")
      (node (ref "R28") (pin "1") (pinfunction "1_1") (pintype "unspecified"))
      (node (ref "RG4") (pin "14") (pinfunction "D_14") (pintype "unspecified"))
      (node (ref "SW28") (pin "2") (pinfunction "2_2") (pintype "unspecified"))
    )
    (net (code "39") (name "U29") (class "Default")
      (node (ref "R29") (pin "1") (pinfunction "1_1") (pintype "unspecified"))
      (node (ref "RG4") (pin "6") (pinfunction "H_6") (pintype "unspecified"))
      (node (ref "SW29") (pin "2") (pinfunction "2_2") (pintype "unspecified"))
    )
    (net (code "40") (name "U30") (class "Default")
      (node (ref "R30") (pin "1") (pinfunction "1_1") (pintype "unspecified"))
      (node (ref "RG4") (pin "5") (pinfunction "G_5") (pintype "unspecified"))
      (node (ref "SW30") (pin "2") (pinfunction "2_2") (pintype "unspecified"))
    )
    (net (code "41") (name "U31") (class "Default")
      (node (ref "R31") (pin "1") (pinfunction "1_1") (pintype "unspecified"))
      (node (ref "RG4") (pin "4") (pinfunction "F_4") (pintype "unspecified"))
      (node (ref "SW31") (pin "2") (pinfunction "2_2") (pintype "unspecified"))
    )
    (net (code "42") (name "U32") (class "Default")
      (node (ref "R32") (pin "1") (pinfunction "1_1") (pintype "unspecified"))
      (node (ref "RG4") (pin "3") (pinfunction "E_3") (pintype "unspecified"))
      (node (ref "SW32") (pin "2") (pinfunction "2_2") (pintype "unspecified"))
    )
    (net (code "43") (name "U33") (class "Default")
      (node (ref "R33") (pin "1") (pinfunction "1_1") (pintype "unspecified"))
      (node (ref "RG5") (pin "11") (pinfunction "A_11") (pintype "unspecified"))
      (node (ref "SW33") (pin "2") (pinfunction "2_2") (pintype "unspecified"))
    )
    (net (code "44") (name "U34") (class "Default")
      (node (ref "R34") (pin "1") (pinfunction "1_1") (pintype "unspecified"))
      (node (ref "RG5") (pin "12") (pinfunction "B_12") (pintype "unspecified"))
      (node (ref "SW34") (pin "2") (pinfunction "2_2") (pintype "unspecified"))
    )
    (net (code "45") (name "U35") (class "Default")
      (node (ref "R35") (pin "1") (pinfunction "1_1") (pintype "unspecified"))
      (node (ref "RG5") (pin "13") (pinfunction "C_13") (pintype "unspecified"))
      (node (ref "SW35") (pin "2") (pinfunction "2_2") (pintype "unspecified"))
    )
    (net (code "46") (name "U36") (class "Default")
      (node (ref "R36") (pin "1") (pinfunction "1_1") (pintype "unspecified"))
      (node (ref "RG5") (pin "14") (pinfunction "D_14") (pintype "unspecified"))
      (node (ref "SW36") (pin "2") (pinfunction "2_2") (pintype "unspecified"))
    )
    (net (code "47") (name "VCC_Port") (class "Default")
      (node (ref "RG1") (pin "16") (pinfunction "VCC_16") (pintype "unspecified"))
      (node (ref "RG2") (pin "16") (pinfunction "VCC_16") (pintype "unspecified"))
      (node (ref "RG3") (pin "16") (pinfunction "VCC_16") (pintype "unspecified"))
      (node (ref "RG4") (pin "16") (pinfunction "VCC_16") (pintype "unspecified"))
      (node (ref "RG5") (pin "16") (pinfunction "VCC_16") (pintype "unspecified"))
      (node (ref "SW1") (pin "1") (pinfunction "1_1") (pintype "unspecified"))
      (node (ref "SW10") (pin "1") (pinfunction "1_1") (pintype "unspecified"))
      (node (ref "SW11") (pin "1") (pinfunction "1_1") (pintype "unspecified"))
      (node (ref "SW12") (pin "1") (pinfunction "1_1") (pintype "unspecified"))
      (node (ref "SW13") (pin "1") (pinfunction "1_1") (pintype "unspecified"))
      (node (ref "SW14") (pin "1") (pinfunction "1_1") (pintype "unspecified"))
      (node (ref "SW15") (pin "1") (pinfunction "1_1") (pintype "unspecified"))
      (node (ref "SW16") (pin "1") (pinfunction "1_1") (pintype "unspecified"))
      (node (ref "SW17") (pin "1") (pinfunction "1_1") (pintype "unspecified"))
      (node (ref "SW18") (pin "1") (pinfunction "1_1") (pintype "unspecified"))
      (node (ref "SW19") (pin "1") (pinfunction "1_1") (pintype "unspecified"))
      (node (ref "SW2") (pin "1") (pinfunction "1_1") (pintype "unspecified"))
      (node (ref "SW20") (pin "1") (pinfunction "1_1") (pintype "unspecified"))
      (node (ref "SW21") (pin "1") (pinfunction "1_1") (pintype "unspecified"))
      (node (ref "SW22") (pin "1") (pinfunction "1_1") (pintype "unspecified"))
      (node (ref "SW23") (pin "1") (pinfunction "1_1") (pintype "unspecified"))
      (node (ref "SW24") (pin "1") (pinfunction "1_1") (pintype "unspecified"))
      (node (ref "SW25") (pin "1") (pinfunction "1_1") (pintype "unspecified"))
      (node (ref "SW26") (pin "1") (pinfunction "1_1") (pintype "unspecified"))
      (node (ref "SW27") (pin "1") (pinfunction "1_1") (pintype "unspecified"))
      (node (ref "SW28") (pin "1") (pinfunction "1_1") (pintype "unspecified"))
      (node (ref "SW29") (pin "1") (pinfunction "1_1") (pintype "unspecified"))
      (node (ref "SW3") (pin "1") (pinfunction "1_1") (pintype "unspecified"))
      (node (ref "SW30") (pin "1") (pinfunction "1_1") (pintype "unspecified"))
      (node (ref "SW31") (pin "1") (pinfunction "1_1") (pintype "unspecified"))
      (node (ref "SW32") (pin "1") (pinfunction "1_1") (pintype "unspecified"))
      (node (ref "SW33") (pin "1") (pinfunction "1_1") (pintype "unspecified"))
      (node (ref "SW34") (pin "1") (pinfunction "1_1") (pintype "unspecified"))
      (node (ref "SW35") (pin "1") (pinfunction "1_1") (pintype "unspecified"))
      (node (ref "SW36") (pin "1") (pinfunction "1_1") (pintype "unspecified"))
      (node (ref "SW4") (pin "1") (pinfunction "1_1") (pintype "unspecified"))
      (node (ref "SW5") (pin "1") (pinfunction "1_1") (pintype "unspecified"))
      (node (ref "SW6") (pin "1") (pinfunction "1_1") (pintype "unspecified"))
      (node (ref "SW7") (pin "1") (pinfunction "1_1") (pintype "unspecified"))
      (node (ref "SW8") (pin "1") (pinfunction "1_1") (pintype "unspecified"))
      (node (ref "SW9") (pin "1") (pinfunction "1_1") (pintype "unspecified"))
    )
    (net (code "48") (name "unconnected-(RG5-E-Pad3)") (class "Default")
      (node (ref "RG5") (pin "3") (pinfunction "E_3") (pintype "unspecified"))
    )
    (net (code "49") (name "unconnected-(RG5-F-Pad4)") (class "Default")
      (node (ref "RG5") (pin "4") (pinfunction "F_4") (pintype "unspecified"))
    )
    (net (code "50") (name "unconnected-(RG5-G-Pad5)") (class "Default")
      (node (ref "RG5") (pin "5") (pinfunction "G_5") (pintype "unspecified"))
    )
    (net (code "51") (name "unconnected-(RG5-H-Pad6)") (class "Default")
      (node (ref "RG5") (pin "6") (pinfunction "H_6") (pintype "unspecified"))
    )
    (net (code "52") (name "unconnected-(RG5-SER-Pad10)") (class "Default")
      (node (ref "RG5") (pin "10") (pinfunction "SER_10") (pintype "unspecified"))
    )
  )
)
